# audio_sw_-_daughter_-_rev_0_1.net
KiCad netlist of a schematic drawn in EAGLE
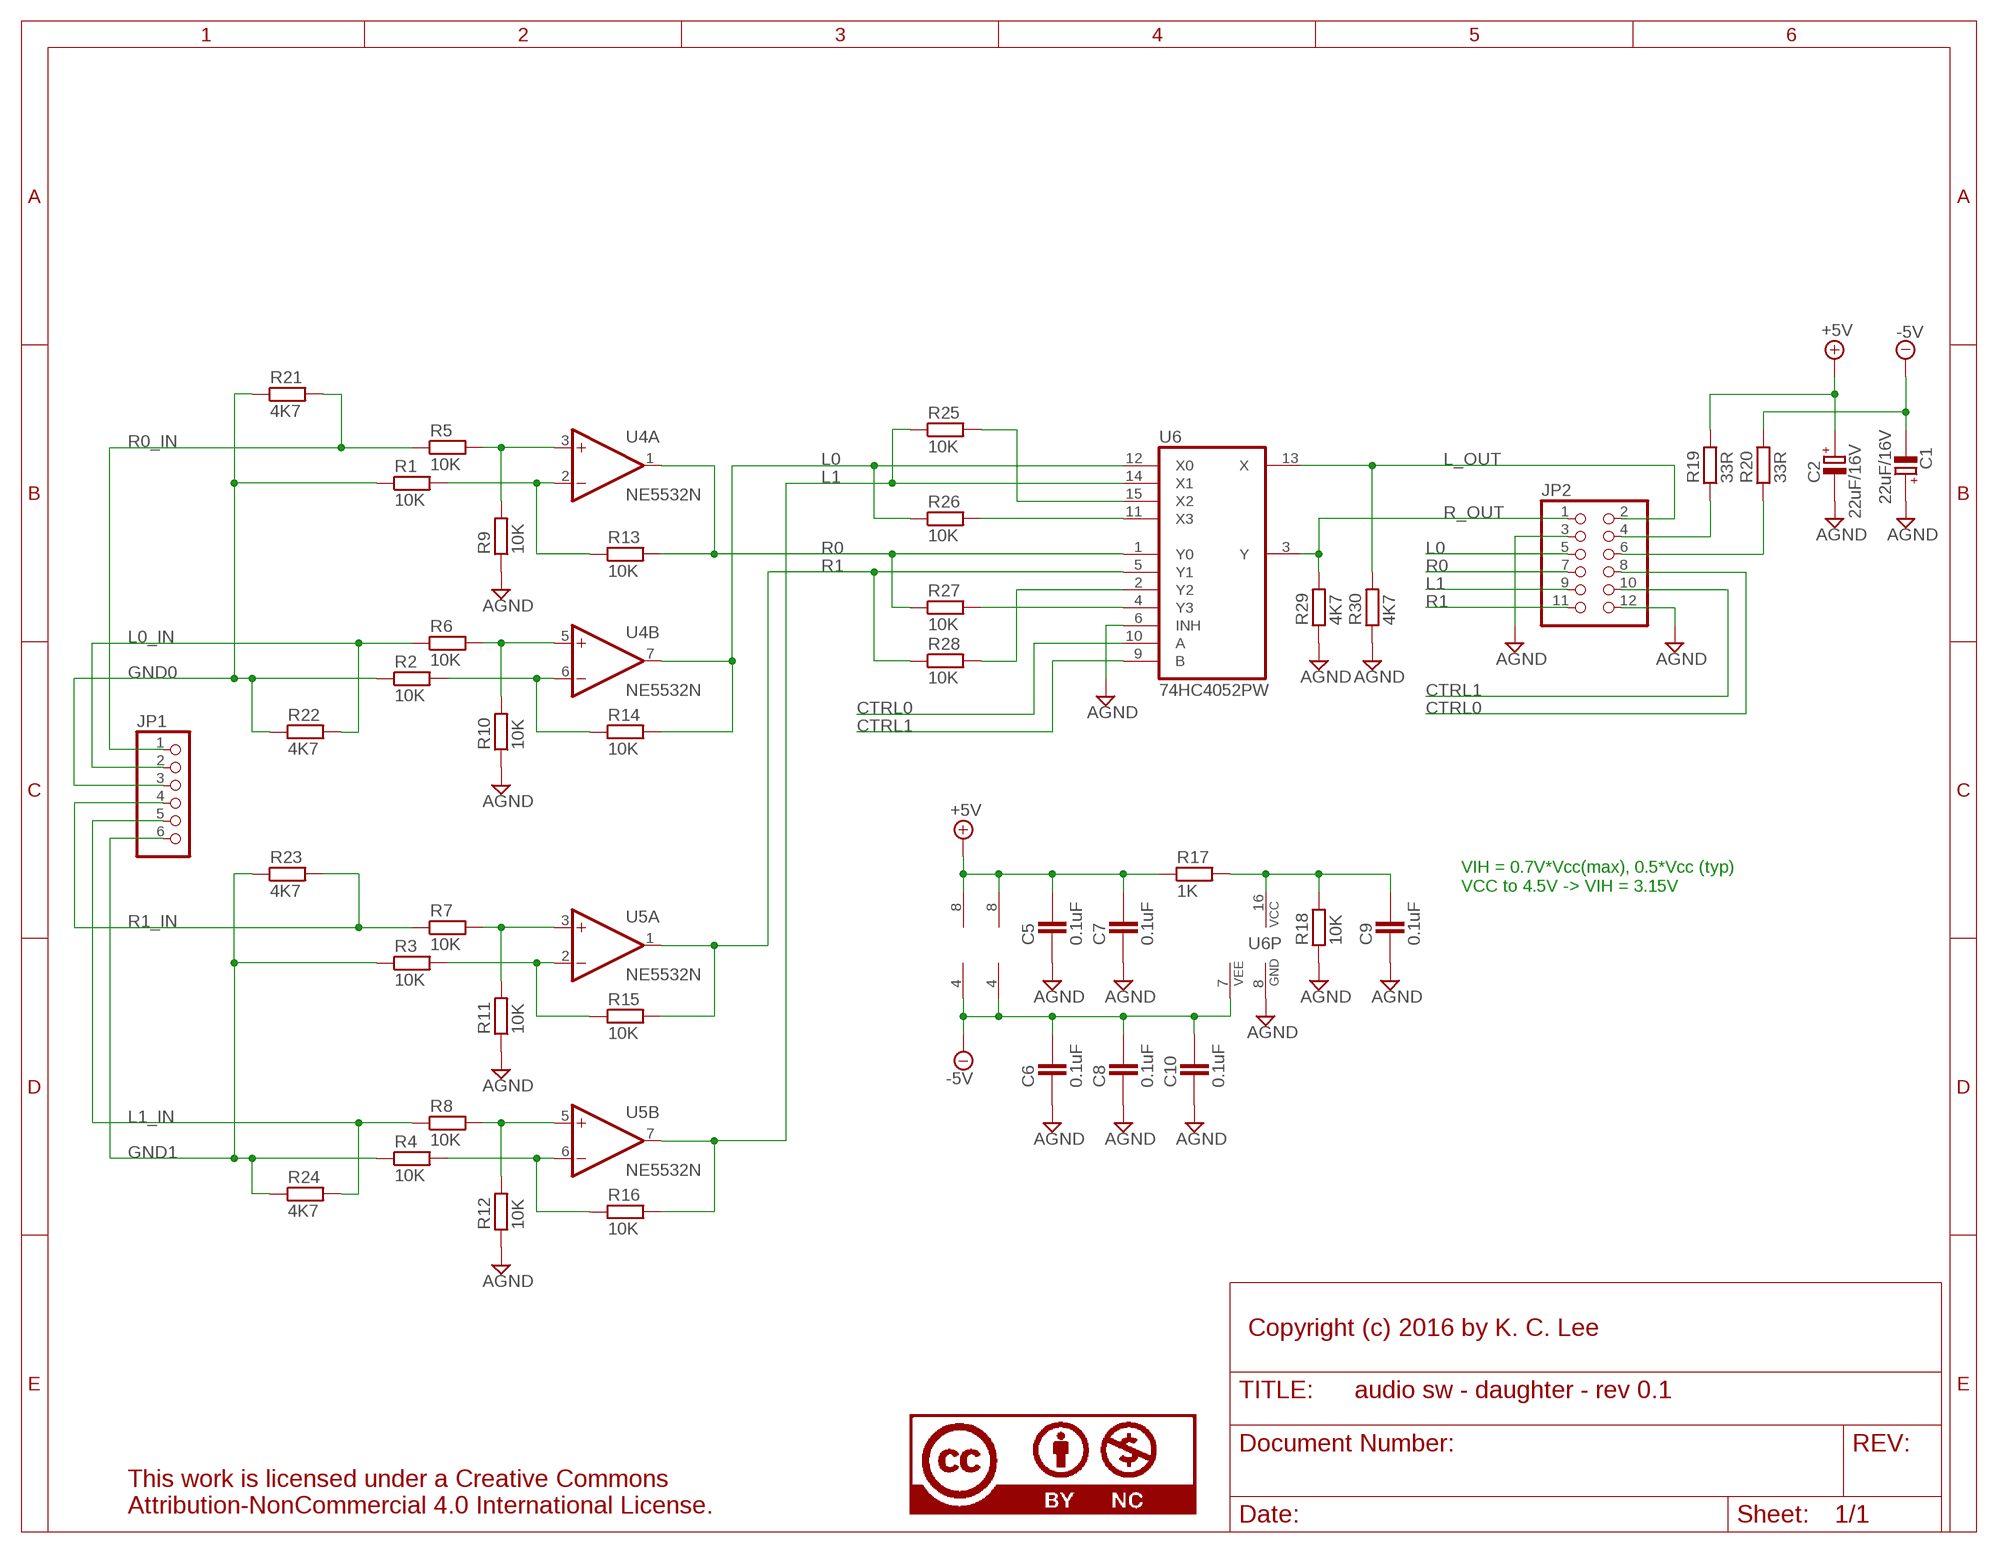
[diagram p0: schematic, sheet 1]

(export (version "E")
  (design (tool "Eeschema 10.0.6"))
  (components
    (comp (ref "C1")
      (value "22uF/16V")
      (footprint "eagle-import:CAPMP6032X280N")
      (libsource (lib "eagle-import") (part "POLARISED_C_CASE"))
    )
    (comp (ref "C2")
      (value "22uF/16V")
      (footprint "eagle-import:CAPMP6032X280N")
      (libsource (lib "eagle-import") (part "POLARISED_C_CASE"))
    )
    (comp (ref "C5")
      (value "0.1uF")
      (footprint "eagle-import:CAPC1608X92N")
      (libsource (lib "eagle-import") (part "CAPACITOR_0603"))
    )
    (comp (ref "C6")
      (value "0.1uF")
      (footprint "eagle-import:CAPC1608X92N")
      (libsource (lib "eagle-import") (part "CAPACITOR_0603"))
    )
    (comp (ref "C7")
      (value "0.1uF")
      (footprint "eagle-import:CAPC1608X92N")
      (libsource (lib "eagle-import") (part "CAPACITOR_0603"))
    )
    (comp (ref "C8")
      (value "0.1uF")
      (footprint "eagle-import:CAPC1608X92N")
      (libsource (lib "eagle-import") (part "CAPACITOR_0603"))
    )
    (comp (ref "C9")
      (value "0.1uF")
      (footprint "eagle-import:CAPC1608X92N")
      (libsource (lib "eagle-import") (part "CAPACITOR_0603"))
    )
    (comp (ref "C10")
      (value "0.1uF")
      (footprint "eagle-import:CAPC1608X92N")
      (libsource (lib "eagle-import") (part "CAPACITOR_0603"))
    )
    (comp (ref "JP1")
      (value "PINHD-1X6")
      (footprint "eagle-import:1X06")
      (libsource (lib "eagle-import") (part "PINHD-1X6"))
    )
    (comp (ref "JP2")
      (value "PINHD-2X6_2.54")
      (footprint "eagle-import:2X06")
      (libsource (lib "eagle-import") (part "PINHD-2X6_2.54"))
    )
    (comp (ref "LICENSE1")
      (value "CC-BY-NC75%")
      (footprint "eagle-import:CC-BY-NC-75")
      (libsource (lib "eagle-import") (part "CC-BY-NC75%"))
    )
    (comp (ref "R1")
      (value "10K")
      (footprint "eagle-import:RESC1608X55N")
      (libsource (lib "eagle-import") (part "RESISTOR_0603"))
    )
    (comp (ref "R2")
      (value "10K")
      (footprint "eagle-import:RESC1608X55N")
      (libsource (lib "eagle-import") (part "RESISTOR_0603"))
    )
    (comp (ref "R3")
      (value "10K")
      (footprint "eagle-import:RESC1608X55N")
      (libsource (lib "eagle-import") (part "RESISTOR_0603"))
    )
    (comp (ref "R4")
      (value "10K")
      (footprint "eagle-import:RESC1608X55N")
      (libsource (lib "eagle-import") (part "RESISTOR_0603"))
    )
    (comp (ref "R5")
      (value "10K")
      (footprint "eagle-import:RESC1608X55N")
      (libsource (lib "eagle-import") (part "RESISTOR_0603"))
    )
    (comp (ref "R6")
      (value "10K")
      (footprint "eagle-import:RESC1608X55N")
      (libsource (lib "eagle-import") (part "RESISTOR_0603"))
    )
    (comp (ref "R7")
      (value "10K")
      (footprint "eagle-import:RESC1608X55N")
      (libsource (lib "eagle-import") (part "RESISTOR_0603"))
    )
    (comp (ref "R8")
      (value "10K")
      (footprint "eagle-import:RESC1608X55N")
      (libsource (lib "eagle-import") (part "RESISTOR_0603"))
    )
    (comp (ref "R9")
      (value "10K")
      (footprint "eagle-import:RESC1608X55N")
      (libsource (lib "eagle-import") (part "RESISTOR_0603"))
    )
    (comp (ref "R10")
      (value "10K")
      (footprint "eagle-import:RESC1608X55N")
      (libsource (lib "eagle-import") (part "RESISTOR_0603"))
    )
    (comp (ref "R11")
      (value "10K")
      (footprint "eagle-import:RESC1608X55N")
      (libsource (lib "eagle-import") (part "RESISTOR_0603"))
    )
    (comp (ref "R12")
      (value "10K")
      (footprint "eagle-import:RESC1608X55N")
      (libsource (lib "eagle-import") (part "RESISTOR_0603"))
    )
    (comp (ref "R13")
      (value "10K")
      (footprint "eagle-import:RESC1608X55N")
      (libsource (lib "eagle-import") (part "RESISTOR_0603"))
    )
    (comp (ref "R14")
      (value "10K")
      (footprint "eagle-import:RESC1608X55N")
      (libsource (lib "eagle-import") (part "RESISTOR_0603"))
    )
    (comp (ref "R15")
      (value "10K")
      (footprint "eagle-import:RESC1608X55N")
      (libsource (lib "eagle-import") (part "RESISTOR_0603"))
    )
    (comp (ref "R16")
      (value "10K")
      (footprint "eagle-import:RESC1608X55N")
      (libsource (lib "eagle-import") (part "RESISTOR_0603"))
    )
    (comp (ref "R17")
      (value "1K")
      (footprint "eagle-import:RESC1608X55N")
      (libsource (lib "eagle-import") (part "RESISTOR_0603"))
    )
    (comp (ref "R18")
      (value "10K")
      (footprint "eagle-import:RESC1608X55N")
      (libsource (lib "eagle-import") (part "RESISTOR_0603"))
    )
    (comp (ref "R19")
      (value "33R")
      (footprint "eagle-import:RESC2012X70N")
      (libsource (lib "eagle-import") (part "RESISTOR_0805"))
    )
    (comp (ref "R20")
      (value "33R")
      (footprint "eagle-import:RESC2012X70N")
      (libsource (lib "eagle-import") (part "RESISTOR_0805"))
    )
    (comp (ref "R21")
      (value "4K7")
      (footprint "eagle-import:RESC1608X55N")
      (libsource (lib "eagle-import") (part "RESISTOR_0603"))
    )
    (comp (ref "R22")
      (value "4K7")
      (footprint "eagle-import:RESC1608X55N")
      (libsource (lib "eagle-import") (part "RESISTOR_0603"))
    )
    (comp (ref "R23")
      (value "4K7")
      (footprint "eagle-import:RESC1608X55N")
      (libsource (lib "eagle-import") (part "RESISTOR_0603"))
    )
    (comp (ref "R24")
      (value "4K7")
      (footprint "eagle-import:RESC1608X55N")
      (libsource (lib "eagle-import") (part "RESISTOR_0603"))
    )
    (comp (ref "R25")
      (value "10K")
      (footprint "eagle-import:RESC1608X55N")
      (libsource (lib "eagle-import") (part "RESISTOR_0603"))
    )
    (comp (ref "R26")
      (value "10K")
      (footprint "eagle-import:RESC1608X55N")
      (libsource (lib "eagle-import") (part "RESISTOR_0603"))
    )
    (comp (ref "R27")
      (value "10K")
      (footprint "eagle-import:RESC1608X55N")
      (libsource (lib "eagle-import") (part "RESISTOR_0603"))
    )
    (comp (ref "R28")
      (value "10K")
      (footprint "eagle-import:RESC1608X55N")
      (libsource (lib "eagle-import") (part "RESISTOR_0603"))
    )
    (comp (ref "R29")
      (value "4K7")
      (footprint "eagle-import:RESC1608X55N")
      (libsource (lib "eagle-import") (part "RESISTOR_0603"))
    )
    (comp (ref "R30")
      (value "4K7")
      (footprint "eagle-import:RESC1608X55N")
      (libsource (lib "eagle-import") (part "RESISTOR_0603"))
    )
    (comp (ref "U4")
      (value "NE5532N")
      (footprint "eagle-import:SO08")
      (fields (field (name "PARTNO") "*"))
      (libsource (lib "eagle-import") (part "LM358D"))
    )
    (comp (ref "U5")
      (value "NE5532N")
      (footprint "eagle-import:SO08")
      (fields (field (name "PARTNO") "*"))
      (libsource (lib "eagle-import") (part "LM358D"))
    )
    (comp (ref "U6")
      (value "74HC4052PW")
      (footprint "eagle-import:TSSOP16")
      (fields (field (name "PARTNO") "*"))
      (libsource (lib "eagle-import") (part "4052PW"))
    )
  )
  (nets
    (net (code "1") (name "+5V") (class "Default")
      (node (ref "C2") (pin "+") (pinfunction "+_+") (pintype "passive"))
      (node (ref "C5") (pin "2") (pinfunction "2_2") (pintype "passive"))
      (node (ref "C7") (pin "2") (pinfunction "2_2") (pintype "passive"))
      (node (ref "R17") (pin "1") (pinfunction "1_1") (pintype "passive"))
      (node (ref "R19") (pin "2") (pinfunction "2_2") (pintype "passive"))
      (node (ref "U4") (pin "8") (pinfunction "V+_8") (pintype "power_in"))
      (node (ref "U5") (pin "8") (pinfunction "V+_8") (pintype "power_in"))
    )
    (net (code "2") (name "-5V") (class "Default")
      (node (ref "C1") (pin "-") (pinfunction "-_-") (pintype "passive"))
      (node (ref "C10") (pin "2") (pinfunction "2_2") (pintype "passive"))
      (node (ref "C6") (pin "2") (pinfunction "2_2") (pintype "passive"))
      (node (ref "C8") (pin "2") (pinfunction "2_2") (pintype "passive"))
      (node (ref "R20") (pin "2") (pinfunction "2_2") (pintype "passive"))
      (node (ref "U4") (pin "4") (pinfunction "V-_4") (pintype "power_in"))
      (node (ref "U5") (pin "4") (pinfunction "V-_4") (pintype "power_in"))
      (node (ref "U6") (pin "7") (pinfunction "VEE_7") (pintype "power_in"))
    )
    (net (code "3") (name "/CTRL0") (class "Default")
      (node (ref "JP2") (pin "8") (pinfunction "8_8") (pintype "passive"))
      (node (ref "U6") (pin "10") (pinfunction "A_10") (pintype "input"))
    )
    (net (code "4") (name "/CTRL1") (class "Default")
      (node (ref "JP2") (pin "10") (pinfunction "10_10") (pintype "passive"))
      (node (ref "U6") (pin "9") (pinfunction "B_9") (pintype "input"))
    )
    (net (code "5") (name "/GND0") (class "Default")
      (node (ref "JP1") (pin "3") (pinfunction "3_3") (pintype "passive"))
      (node (ref "R1") (pin "1") (pinfunction "1_1") (pintype "passive"))
      (node (ref "R2") (pin "1") (pinfunction "1_1") (pintype "passive"))
      (node (ref "R21") (pin "1") (pinfunction "1_1") (pintype "passive"))
      (node (ref "R22") (pin "1") (pinfunction "1_1") (pintype "passive"))
    )
    (net (code "6") (name "/GND1") (class "Default")
      (node (ref "JP1") (pin "6") (pinfunction "6_6") (pintype "passive"))
      (node (ref "R23") (pin "1") (pinfunction "1_1") (pintype "passive"))
      (node (ref "R24") (pin "1") (pinfunction "1_1") (pintype "passive"))
      (node (ref "R3") (pin "1") (pinfunction "1_1") (pintype "passive"))
      (node (ref "R4") (pin "1") (pinfunction "1_1") (pintype "passive"))
    )
    (net (code "7") (name "/L0") (class "Default")
      (node (ref "JP2") (pin "5") (pinfunction "5_5") (pintype "passive"))
      (node (ref "R14") (pin "2") (pinfunction "2_2") (pintype "passive"))
      (node (ref "R26") (pin "1") (pinfunction "1_1") (pintype "passive"))
      (node (ref "U4") (pin "7") (pinfunction "OUT_7") (pintype "output"))
      (node (ref "U6") (pin "12") (pinfunction "X0_12") (pintype "bidirectional"))
    )
    (net (code "8") (name "/L0_IN") (class "Default")
      (node (ref "JP1") (pin "2") (pinfunction "2_2") (pintype "passive"))
      (node (ref "R22") (pin "2") (pinfunction "2_2") (pintype "passive"))
      (node (ref "R6") (pin "1") (pinfunction "1_1") (pintype "passive"))
    )
    (net (code "9") (name "/L1") (class "Default")
      (node (ref "JP2") (pin "9") (pinfunction "9_9") (pintype "passive"))
      (node (ref "R16") (pin "2") (pinfunction "2_2") (pintype "passive"))
      (node (ref "R25") (pin "1") (pinfunction "1_1") (pintype "passive"))
      (node (ref "U5") (pin "7") (pinfunction "OUT_7") (pintype "output"))
      (node (ref "U6") (pin "14") (pinfunction "X1_14") (pintype "bidirectional"))
    )
    (net (code "10") (name "/L1_IN") (class "Default")
      (node (ref "JP1") (pin "5") (pinfunction "5_5") (pintype "passive"))
      (node (ref "R24") (pin "2") (pinfunction "2_2") (pintype "passive"))
      (node (ref "R8") (pin "1") (pinfunction "1_1") (pintype "passive"))
    )
    (net (code "11") (name "/L_OUT") (class "Default")
      (node (ref "JP2") (pin "2") (pinfunction "2_2") (pintype "passive"))
      (node (ref "R30") (pin "2") (pinfunction "2_2") (pintype "passive"))
      (node (ref "U6") (pin "13") (pinfunction "X_13") (pintype "bidirectional"))
    )
    (net (code "12") (name "/R0") (class "Default")
      (node (ref "JP2") (pin "7") (pinfunction "7_7") (pintype "passive"))
      (node (ref "R13") (pin "2") (pinfunction "2_2") (pintype "passive"))
      (node (ref "R27") (pin "1") (pinfunction "1_1") (pintype "passive"))
      (node (ref "U4") (pin "1") (pinfunction "OUT_1") (pintype "output"))
      (node (ref "U6") (pin "1") (pinfunction "Y0_1") (pintype "bidirectional"))
    )
    (net (code "13") (name "/R0_IN") (class "Default")
      (node (ref "JP1") (pin "1") (pinfunction "1_1") (pintype "passive"))
      (node (ref "R21") (pin "2") (pinfunction "2_2") (pintype "passive"))
      (node (ref "R5") (pin "1") (pinfunction "1_1") (pintype "passive"))
    )
    (net (code "14") (name "/R1") (class "Default")
      (node (ref "JP2") (pin "11") (pinfunction "11_11") (pintype "passive"))
      (node (ref "R15") (pin "2") (pinfunction "2_2") (pintype "passive"))
      (node (ref "R28") (pin "1") (pinfunction "1_1") (pintype "passive"))
      (node (ref "U5") (pin "1") (pinfunction "OUT_1") (pintype "output"))
      (node (ref "U6") (pin "5") (pinfunction "Y1_5") (pintype "bidirectional"))
    )
    (net (code "15") (name "/R1_IN") (class "Default")
      (node (ref "JP1") (pin "4") (pinfunction "4_4") (pintype "passive"))
      (node (ref "R23") (pin "2") (pinfunction "2_2") (pintype "passive"))
      (node (ref "R7") (pin "1") (pinfunction "1_1") (pintype "passive"))
    )
    (net (code "16") (name "/R_OUT") (class "Default")
      (node (ref "JP2") (pin "1") (pinfunction "1_1") (pintype "passive"))
      (node (ref "R29") (pin "2") (pinfunction "2_2") (pintype "passive"))
      (node (ref "U6") (pin "3") (pinfunction "Y_3") (pintype "bidirectional"))
    )
    (net (code "17") (name "AGND") (class "Default")
      (node (ref "C1") (pin "+") (pinfunction "+_+") (pintype "passive"))
      (node (ref "C10") (pin "1") (pinfunction "1_1") (pintype "passive"))
      (node (ref "C2") (pin "-") (pinfunction "-_-") (pintype "passive"))
      (node (ref "C5") (pin "1") (pinfunction "1_1") (pintype "passive"))
      (node (ref "C6") (pin "1") (pinfunction "1_1") (pintype "passive"))
      (node (ref "C7") (pin "1") (pinfunction "1_1") (pintype "passive"))
      (node (ref "C8") (pin "1") (pinfunction "1_1") (pintype "passive"))
      (node (ref "C9") (pin "1") (pinfunction "1_1") (pintype "passive"))
      (node (ref "JP2") (pin "12") (pinfunction "12_12") (pintype "passive"))
      (node (ref "JP2") (pin "3") (pinfunction "3_3") (pintype "passive"))
      (node (ref "R10") (pin "1") (pinfunction "1_1") (pintype "passive"))
      (node (ref "R11") (pin "1") (pinfunction "1_1") (pintype "passive"))
      (node (ref "R12") (pin "1") (pinfunction "1_1") (pintype "passive"))
      (node (ref "R18") (pin "1") (pinfunction "1_1") (pintype "passive"))
      (node (ref "R29") (pin "1") (pinfunction "1_1") (pintype "passive"))
      (node (ref "R30") (pin "1") (pinfunction "1_1") (pintype "passive"))
      (node (ref "R9") (pin "1") (pinfunction "1_1") (pintype "passive"))
      (node (ref "U6") (pin "6") (pinfunction "INH_6") (pintype "input"))
      (node (ref "U6") (pin "8") (pinfunction "GND_8") (pintype "power_in"))
    )
    (net (code "18") (name "Net-(JP2-Pad4)") (class "Default")
      (node (ref "JP2") (pin "4") (pinfunction "4_4") (pintype "passive"))
      (node (ref "R19") (pin "1") (pinfunction "1_1") (pintype "passive"))
    )
    (net (code "19") (name "Net-(JP2-Pad6)") (class "Default")
      (node (ref "JP2") (pin "6") (pinfunction "6_6") (pintype "passive"))
      (node (ref "R20") (pin "1") (pinfunction "1_1") (pintype "passive"))
    )
    (net (code "20") (name "Net-(U4A-+IN)") (class "Default")
      (node (ref "R5") (pin "2") (pinfunction "2_2") (pintype "passive"))
      (node (ref "R9") (pin "2") (pinfunction "2_2") (pintype "passive"))
      (node (ref "U4") (pin "3") (pinfunction "+IN_3") (pintype "input"))
    )
    (net (code "21") (name "Net-(U4A--IN)") (class "Default")
      (node (ref "R1") (pin "2") (pinfunction "2_2") (pintype "passive"))
      (node (ref "R13") (pin "1") (pinfunction "1_1") (pintype "passive"))
      (node (ref "U4") (pin "2") (pinfunction "-IN_2") (pintype "input"))
    )
    (net (code "22") (name "Net-(U4B-+IN)") (class "Default")
      (node (ref "R10") (pin "2") (pinfunction "2_2") (pintype "passive"))
      (node (ref "R6") (pin "2") (pinfunction "2_2") (pintype "passive"))
      (node (ref "U4") (pin "5") (pinfunction "+IN_5") (pintype "input"))
    )
    (net (code "23") (name "Net-(U4B--IN)") (class "Default")
      (node (ref "R14") (pin "1") (pinfunction "1_1") (pintype "passive"))
      (node (ref "R2") (pin "2") (pinfunction "2_2") (pintype "passive"))
      (node (ref "U4") (pin "6") (pinfunction "-IN_6") (pintype "input"))
    )
    (net (code "24") (name "Net-(U5A-+IN)") (class "Default")
      (node (ref "R11") (pin "2") (pinfunction "2_2") (pintype "passive"))
      (node (ref "R7") (pin "2") (pinfunction "2_2") (pintype "passive"))
      (node (ref "U5") (pin "3") (pinfunction "+IN_3") (pintype "input"))
    )
    (net (code "25") (name "Net-(U5A--IN)") (class "Default")
      (node (ref "R15") (pin "1") (pinfunction "1_1") (pintype "passive"))
      (node (ref "R3") (pin "2") (pinfunction "2_2") (pintype "passive"))
      (node (ref "U5") (pin "2") (pinfunction "-IN_2") (pintype "input"))
    )
    (net (code "26") (name "Net-(U5B-+IN)") (class "Default")
      (node (ref "R12") (pin "2") (pinfunction "2_2") (pintype "passive"))
      (node (ref "R8") (pin "2") (pinfunction "2_2") (pintype "passive"))
      (node (ref "U5") (pin "5") (pinfunction "+IN_5") (pintype "input"))
    )
    (net (code "27") (name "Net-(U5B--IN)") (class "Default")
      (node (ref "R16") (pin "1") (pinfunction "1_1") (pintype "passive"))
      (node (ref "R4") (pin "2") (pinfunction "2_2") (pintype "passive"))
      (node (ref "U5") (pin "6") (pinfunction "-IN_6") (pintype "input"))
    )
    (net (code "28") (name "Net-(U6A-X2)") (class "Default")
      (node (ref "R25") (pin "2") (pinfunction "2_2") (pintype "passive"))
      (node (ref "U6") (pin "15") (pinfunction "X2_15") (pintype "bidirectional"))
    )
    (net (code "29") (name "Net-(U6A-X3)") (class "Default")
      (node (ref "R26") (pin "2") (pinfunction "2_2") (pintype "passive"))
      (node (ref "U6") (pin "11") (pinfunction "X3_11") (pintype "bidirectional"))
    )
    (net (code "30") (name "Net-(U6A-Y2)") (class "Default")
      (node (ref "R28") (pin "2") (pinfunction "2_2") (pintype "passive"))
      (node (ref "U6") (pin "2") (pinfunction "Y2_2") (pintype "bidirectional"))
    )
    (net (code "31") (name "Net-(U6A-Y3)") (class "Default")
      (node (ref "R27") (pin "2") (pinfunction "2_2") (pintype "passive"))
      (node (ref "U6") (pin "4") (pinfunction "Y3_4") (pintype "bidirectional"))
    )
    (net (code "32") (name "Net-(U6B-VCC)") (class "Default")
      (node (ref "C9") (pin "2") (pinfunction "2_2") (pintype "passive"))
      (node (ref "R17") (pin "2") (pinfunction "2_2") (pintype "passive"))
      (node (ref "R18") (pin "2") (pinfunction "2_2") (pintype "passive"))
      (node (ref "U6") (pin "16") (pinfunction "VCC_16") (pintype "power_in"))
    )
  )
)
